# module_SIM800C.net
KiCad netlist of a schematic drawn in EAGLE
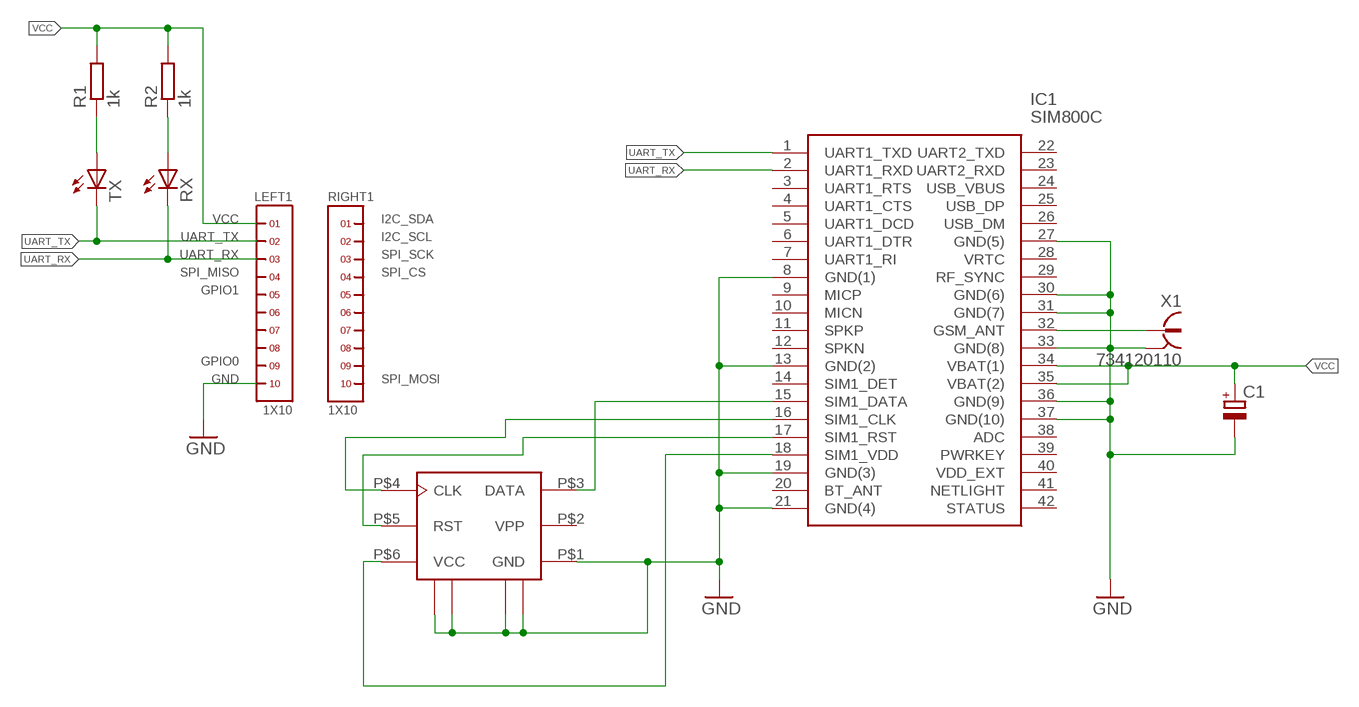
[diagram p0: schematic, sheet 1]

(export (version "E")
  (design (tool "Eeschema 10.0.6"))
  (components
    (comp (ref "C1")
      (value "CPOL-EUSMCD")
      (footprint "eagle-import:SMC_D")
      (libsource (lib "eagle-import") (part "CPOL-EUSMCD"))
    )
    (comp (ref "IC1")
      (value "SIM800C")
      (footprint "eagle-import:SIM800C")
      (fields (field (name "MANUFACTURER_PART_NUMBER") "sim800c"))
      (libsource (lib "eagle-import") (part "SIM800C"))
    )
    (comp (ref "LEFT1")
      (value "1X10")
      (footprint "eagle-import:1X10")
      (libsource (lib "eagle-import") (part "1X10"))
    )
    (comp (ref "R1")
      (value "1k")
      (footprint "eagle-import:R0603")
      (libsource (lib "eagle-import") (part "R-EU_R0603"))
    )
    (comp (ref "R2")
      (value "1k")
      (footprint "eagle-import:R0603")
      (libsource (lib "eagle-import") (part "R-EU_R0603"))
    )
    (comp (ref "RIGHT1")
      (value "1X10")
      (footprint "eagle-import:1X10")
      (libsource (lib "eagle-import") (part "1X10"))
    )
    (comp (ref "RX")
      (value "LEDCHIPLED_0603")
      (footprint "eagle-import:CHIPLED_0603")
      (libsource (lib "eagle-import") (part "LEDCHIPLED_0603"))
    )
    (comp (ref "TX")
      (value "LEDCHIPLED_0603")
      (footprint "eagle-import:CHIPLED_0603")
      (libsource (lib "eagle-import") (part "LEDCHIPLED_0603"))
    )
    (comp (ref "U$1")
      (value "C707-10M006-136-2")
      (footprint "eagle-import:C707-10M006-136-2")
      (libsource (lib "eagle-import") (part "C707-10M006-136-2"))
    )
    (comp (ref "X1")
      (value "734120110")
      (footprint "eagle-import:734120110")
      (libsource (lib "eagle-import") (part "734120110"))
    )
  )
  (nets
    (net (code "1") (name "/VPP") (class "Default")
      (node (ref "U$1") (pin "P$2") (pinfunction "VPP_P$2") (pintype "power_in"))
    )
    (net (code "2") (name "GND") (class "Default")
      (node (ref "C1") (pin "-") (pinfunction "-_-") (pintype "passive"))
      (node (ref "IC1") (pin "13") (pinfunction "GND(2)_13") (pintype "input"))
      (node (ref "IC1") (pin "19") (pinfunction "GND(3)_19") (pintype "input"))
      (node (ref "IC1") (pin "21") (pinfunction "GND(4)_21") (pintype "input"))
      (node (ref "IC1") (pin "27") (pinfunction "GND(5)_27") (pintype "input"))
      (node (ref "IC1") (pin "30") (pinfunction "GND(6)_30") (pintype "input"))
      (node (ref "IC1") (pin "31") (pinfunction "GND(7)_31") (pintype "input"))
      (node (ref "IC1") (pin "33") (pinfunction "GND(8)_33") (pintype "input"))
      (node (ref "IC1") (pin "36") (pinfunction "GND(9)_36") (pintype "input"))
      (node (ref "IC1") (pin "37") (pinfunction "GND(10)_37") (pintype "input"))
      (node (ref "IC1") (pin "8") (pinfunction "GND(1)_8") (pintype "input"))
      (node (ref "LEFT1") (pin "10") (pinfunction "10_10") (pintype "bidirectional"))
      (node (ref "U$1") (pin "P$1") (pinfunction "GND_P$1") (pintype "power_in"))
      (node (ref "U$1") (pin "P$10") (pinfunction "GND4_P$10") (pintype "power_in"))
      (node (ref "U$1") (pin "P$7") (pinfunction "GND1_P$7") (pintype "power_in"))
      (node (ref "U$1") (pin "P$8") (pinfunction "GND2_P$8") (pintype "power_in"))
      (node (ref "U$1") (pin "P$9") (pinfunction "GND3_P$9") (pintype "power_in"))
      (node (ref "X1") (pin "S@1") (pinfunction "2_S@1") (pintype "passive"))
      (node (ref "X1") (pin "S@2") (pinfunction "2_S@2") (pintype "passive"))
      (node (ref "X1") (pin "S@3") (pinfunction "2_S@3") (pintype "passive"))
    )
    (net (code "3") (name "Net-(IC1-GSM_ANT)") (class "Default")
      (node (ref "IC1") (pin "32") (pinfunction "GSM_ANT_32") (pintype "input"))
      (node (ref "X1") (pin "1") (pinfunction "1_1") (pintype "passive"))
    )
    (net (code "4") (name "Net-(IC1-SIM1_CLK)") (class "Default")
      (node (ref "IC1") (pin "16") (pinfunction "SIM1_CLK_16") (pintype "input"))
      (node (ref "U$1") (pin "P$4") (pinfunction "CLK_P$4") (pintype "input"))
    )
    (net (code "5") (name "Net-(IC1-SIM1_DATA)") (class "Default")
      (node (ref "IC1") (pin "15") (pinfunction "SIM1_DATA_15") (pintype "input"))
      (node (ref "U$1") (pin "P$3") (pinfunction "DATA_P$3") (pintype "bidirectional"))
    )
    (net (code "6") (name "Net-(IC1-SIM1_RST)") (class "Default")
      (node (ref "IC1") (pin "17") (pinfunction "SIM1_RST_17") (pintype "input"))
      (node (ref "U$1") (pin "P$5") (pinfunction "RST_P$5") (pintype "input"))
    )
    (net (code "7") (name "Net-(IC1-SIM1_VDD)") (class "Default")
      (node (ref "IC1") (pin "18") (pinfunction "SIM1_VDD_18") (pintype "input"))
      (node (ref "U$1") (pin "P$6") (pinfunction "VCC_P$6") (pintype "power_in"))
    )
    (net (code "8") (name "Net-(R1-Pad1)") (class "Default")
      (node (ref "R1") (pin "1") (pinfunction "1_1") (pintype "passive"))
      (node (ref "TX") (pin "A") (pinfunction "A_A") (pintype "passive"))
    )
    (net (code "9") (name "Net-(R2-Pad1)") (class "Default")
      (node (ref "R2") (pin "1") (pinfunction "1_1") (pintype "passive"))
      (node (ref "RX") (pin "A") (pinfunction "A_A") (pintype "passive"))
    )
    (net (code "10") (name "UART_RX") (class "Default")
      (node (ref "IC1") (pin "2") (pinfunction "UART1_RXD_2") (pintype "input"))
      (node (ref "LEFT1") (pin "3") (pinfunction "3_3") (pintype "bidirectional"))
      (node (ref "RX") (pin "C") (pinfunction "C_C") (pintype "passive"))
    )
    (net (code "11") (name "UART_TX") (class "Default")
      (node (ref "IC1") (pin "1") (pinfunction "UART1_TXD_1") (pintype "input"))
      (node (ref "LEFT1") (pin "2") (pinfunction "2_2") (pintype "bidirectional"))
      (node (ref "TX") (pin "C") (pinfunction "C_C") (pintype "passive"))
    )
    (net (code "12") (name "VCC") (class "Default")
      (node (ref "C1") (pin "+") (pinfunction "+_+") (pintype "passive"))
      (node (ref "IC1") (pin "34") (pinfunction "VBAT(1)_34") (pintype "input"))
      (node (ref "IC1") (pin "35") (pinfunction "VBAT(2)_35") (pintype "input"))
      (node (ref "LEFT1") (pin "1") (pinfunction "1_1") (pintype "bidirectional"))
      (node (ref "R1") (pin "2") (pinfunction "2_2") (pintype "passive"))
      (node (ref "R2") (pin "2") (pinfunction "2_2") (pintype "passive"))
    )
    (net (code "13") (name "unconnected-(IC1-ADC-Pad38)") (class "Default")
      (node (ref "IC1") (pin "38") (pinfunction "ADC_38") (pintype "input"))
    )
    (net (code "14") (name "unconnected-(IC1-BT_ANT-Pad20)") (class "Default")
      (node (ref "IC1") (pin "20") (pinfunction "BT_ANT_20") (pintype "input"))
    )
    (net (code "15") (name "unconnected-(IC1-MICN-Pad10)") (class "Default")
      (node (ref "IC1") (pin "10") (pinfunction "MICN_10") (pintype "input"))
    )
    (net (code "16") (name "unconnected-(IC1-MICP-Pad9)") (class "Default")
      (node (ref "IC1") (pin "9") (pinfunction "MICP_9") (pintype "input"))
    )
    (net (code "17") (name "unconnected-(IC1-NETLIGHT-Pad41)") (class "Default")
      (node (ref "IC1") (pin "41") (pinfunction "NETLIGHT_41") (pintype "input"))
    )
    (net (code "18") (name "unconnected-(IC1-PWRKEY-Pad39)") (class "Default")
      (node (ref "IC1") (pin "39") (pinfunction "PWRKEY_39") (pintype "input"))
    )
    (net (code "19") (name "unconnected-(IC1-RF_SYNC-Pad29)") (class "Default")
      (node (ref "IC1") (pin "29") (pinfunction "RF_SYNC_29") (pintype "input"))
    )
    (net (code "20") (name "unconnected-(IC1-SIM1_DET-Pad14)") (class "Default")
      (node (ref "IC1") (pin "14") (pinfunction "SIM1_DET_14") (pintype "input"))
    )
    (net (code "21") (name "unconnected-(IC1-SPKN-Pad12)") (class "Default")
      (node (ref "IC1") (pin "12") (pinfunction "SPKN_12") (pintype "input"))
    )
    (net (code "22") (name "unconnected-(IC1-SPKP-Pad11)") (class "Default")
      (node (ref "IC1") (pin "11") (pinfunction "SPKP_11") (pintype "input"))
    )
    (net (code "23") (name "unconnected-(IC1-STATUS-Pad42)") (class "Default")
      (node (ref "IC1") (pin "42") (pinfunction "STATUS_42") (pintype "input"))
    )
    (net (code "24") (name "unconnected-(IC1-UART1_CTS-Pad4)") (class "Default")
      (node (ref "IC1") (pin "4") (pinfunction "UART1_CTS_4") (pintype "input"))
    )
    (net (code "25") (name "unconnected-(IC1-UART1_DCD-Pad5)") (class "Default")
      (node (ref "IC1") (pin "5") (pinfunction "UART1_DCD_5") (pintype "input"))
    )
    (net (code "26") (name "unconnected-(IC1-UART1_DTR-Pad6)") (class "Default")
      (node (ref "IC1") (pin "6") (pinfunction "UART1_DTR_6") (pintype "input"))
    )
    (net (code "27") (name "unconnected-(IC1-UART1_RI-Pad7)") (class "Default")
      (node (ref "IC1") (pin "7") (pinfunction "UART1_RI_7") (pintype "input"))
    )
    (net (code "28") (name "unconnected-(IC1-UART1_RTS-Pad3)") (class "Default")
      (node (ref "IC1") (pin "3") (pinfunction "UART1_RTS_3") (pintype "input"))
    )
    (net (code "29") (name "unconnected-(IC1-UART2_RXD-Pad23)") (class "Default")
      (node (ref "IC1") (pin "23") (pinfunction "UART2_RXD_23") (pintype "input"))
    )
    (net (code "30") (name "unconnected-(IC1-UART2_TXD-Pad22)") (class "Default")
      (node (ref "IC1") (pin "22") (pinfunction "UART2_TXD_22") (pintype "input"))
    )
    (net (code "31") (name "unconnected-(IC1-USB_DM-Pad26)") (class "Default")
      (node (ref "IC1") (pin "26") (pinfunction "USB_DM_26") (pintype "input"))
    )
    (net (code "32") (name "unconnected-(IC1-USB_DP-Pad25)") (class "Default")
      (node (ref "IC1") (pin "25") (pinfunction "USB_DP_25") (pintype "input"))
    )
    (net (code "33") (name "unconnected-(IC1-USB_VBUS-Pad24)") (class "Default")
      (node (ref "IC1") (pin "24") (pinfunction "USB_VBUS_24") (pintype "input"))
    )
    (net (code "34") (name "unconnected-(IC1-VDD_EXT-Pad40)") (class "Default")
      (node (ref "IC1") (pin "40") (pinfunction "VDD_EXT_40") (pintype "input"))
    )
    (net (code "35") (name "unconnected-(IC1-VRTC-Pad28)") (class "Default")
      (node (ref "IC1") (pin "28") (pinfunction "VRTC_28") (pintype "input"))
    )
    (net (code "36") (name "unconnected-(LEFT1-Pad4)") (class "Default")
      (node (ref "LEFT1") (pin "4") (pinfunction "4_4") (pintype "bidirectional"))
    )
    (net (code "37") (name "unconnected-(LEFT1-Pad5)") (class "Default")
      (node (ref "LEFT1") (pin "5") (pinfunction "5_5") (pintype "bidirectional"))
    )
    (net (code "38") (name "unconnected-(LEFT1-Pad6)") (class "Default")
      (node (ref "LEFT1") (pin "6") (pinfunction "6_6") (pintype "bidirectional"))
    )
    (net (code "39") (name "unconnected-(LEFT1-Pad7)") (class "Default")
      (node (ref "LEFT1") (pin "7") (pinfunction "7_7") (pintype "bidirectional"))
    )
    (net (code "40") (name "unconnected-(LEFT1-Pad8)") (class "Default")
      (node (ref "LEFT1") (pin "8") (pinfunction "8_8") (pintype "bidirectional"))
    )
    (net (code "41") (name "unconnected-(LEFT1-Pad9)") (class "Default")
      (node (ref "LEFT1") (pin "9") (pinfunction "9_9") (pintype "bidirectional"))
    )
    (net (code "42") (name "unconnected-(RIGHT1-Pad1)") (class "Default")
      (node (ref "RIGHT1") (pin "1") (pinfunction "1_1") (pintype "bidirectional"))
    )
    (net (code "43") (name "unconnected-(RIGHT1-Pad2)") (class "Default")
      (node (ref "RIGHT1") (pin "2") (pinfunction "2_2") (pintype "bidirectional"))
    )
    (net (code "44") (name "unconnected-(RIGHT1-Pad3)") (class "Default")
      (node (ref "RIGHT1") (pin "3") (pinfunction "3_3") (pintype "bidirectional"))
    )
    (net (code "45") (name "unconnected-(RIGHT1-Pad4)") (class "Default")
      (node (ref "RIGHT1") (pin "4") (pinfunction "4_4") (pintype "bidirectional"))
    )
    (net (code "46") (name "unconnected-(RIGHT1-Pad5)") (class "Default")
      (node (ref "RIGHT1") (pin "5") (pinfunction "5_5") (pintype "bidirectional"))
    )
    (net (code "47") (name "unconnected-(RIGHT1-Pad6)") (class "Default")
      (node (ref "RIGHT1") (pin "6") (pinfunction "6_6") (pintype "bidirectional"))
    )
    (net (code "48") (name "unconnected-(RIGHT1-Pad7)") (class "Default")
      (node (ref "RIGHT1") (pin "7") (pinfunction "7_7") (pintype "bidirectional"))
    )
    (net (code "49") (name "unconnected-(RIGHT1-Pad8)") (class "Default")
      (node (ref "RIGHT1") (pin "8") (pinfunction "8_8") (pintype "bidirectional"))
    )
    (net (code "50") (name "unconnected-(RIGHT1-Pad9)") (class "Default")
      (node (ref "RIGHT1") (pin "9") (pinfunction "9_9") (pintype "bidirectional"))
    )
    (net (code "51") (name "unconnected-(RIGHT1-Pad10)") (class "Default")
      (node (ref "RIGHT1") (pin "10") (pinfunction "10_10") (pintype "bidirectional"))
    )
  )
)
